# untitled.net
KiCad netlist of a schematic drawn in EAGLE
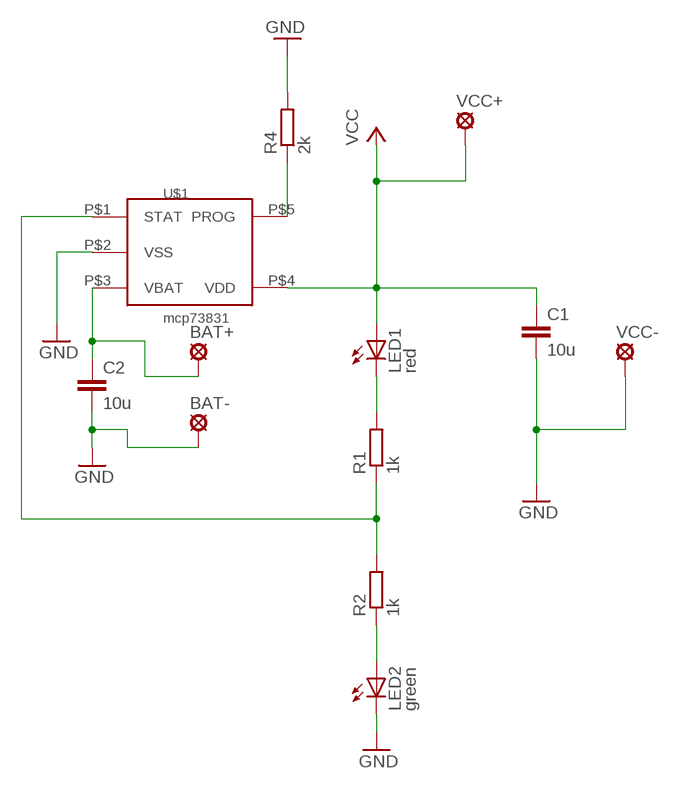
[diagram p0: schematic, sheet 1]

(export (version "E")
  (design (tool "Eeschema 10.0.6"))
  (components
    (comp (ref "BAT+")
      (value "LSP10")
      (footprint "eagle-import:LSP10")
      (libsource (lib "eagle-import") (part "LSP10"))
    )
    (comp (ref "BAT-")
      (value "LSP10")
      (footprint "eagle-import:LSP10")
      (libsource (lib "eagle-import") (part "LSP10"))
    )
    (comp (ref "C1")
      (value "10u")
      (footprint "eagle-import:C0805")
      (libsource (lib "eagle-import") (part "C-EUC0805"))
    )
    (comp (ref "C2")
      (value "10u")
      (footprint "eagle-import:C0805")
      (libsource (lib "eagle-import") (part "C-EUC0805"))
    )
    (comp (ref "LED1")
      (value "red")
      (footprint "eagle-import:CHIPLED_0805")
      (libsource (lib "eagle-import") (part "LEDCHIPLED_0805"))
    )
    (comp (ref "LED2")
      (value "green")
      (footprint "eagle-import:CHIPLED_0805")
      (libsource (lib "eagle-import") (part "LEDCHIPLED_0805"))
    )
    (comp (ref "R1")
      (value "1k")
      (footprint "eagle-import:M1206")
      (libsource (lib "eagle-import") (part "R-EU_M1206"))
    )
    (comp (ref "R2")
      (value "1k")
      (footprint "eagle-import:M1206")
      (libsource (lib "eagle-import") (part "R-EU_M1206"))
    )
    (comp (ref "R4")
      (value "2k")
      (footprint "eagle-import:M1206")
      (libsource (lib "eagle-import") (part "R-EU_M1206"))
    )
    (comp (ref "U$1")
      (value "mcp73831")
      (footprint "eagle-import:5PIN_SOT23")
      (libsource (lib "eagle-import") (part "MCP73831"))
    )
    (comp (ref "VCC+")
      (value "LSP10")
      (footprint "eagle-import:LSP10")
      (libsource (lib "eagle-import") (part "LSP10"))
    )
    (comp (ref "VCC-")
      (value "LSP10")
      (footprint "eagle-import:LSP10")
      (libsource (lib "eagle-import") (part "LSP10"))
    )
  )
  (nets
    (net (code "1") (name "GND") (class "Default")
      (node (ref "BAT-") (pin "MP") (pinfunction "MP_MP") (pintype "passive"))
      (node (ref "C1") (pin "2") (pinfunction "2_2") (pintype "passive"))
      (node (ref "C2") (pin "2") (pinfunction "2_2") (pintype "passive"))
      (node (ref "LED2") (pin "C") (pinfunction "C_C") (pintype "passive"))
      (node (ref "R4") (pin "2") (pinfunction "2_2") (pintype "passive"))
      (node (ref "U$1") (pin "P$2") (pinfunction "VSS_P$2") (pintype "bidirectional"))
      (node (ref "VCC-") (pin "MP") (pinfunction "MP_MP") (pintype "passive"))
    )
    (net (code "2") (name "Net-(LED1-PadC)") (class "Default")
      (node (ref "LED1") (pin "C") (pinfunction "C_C") (pintype "passive"))
      (node (ref "R1") (pin "2") (pinfunction "2_2") (pintype "passive"))
    )
    (net (code "3") (name "Net-(LED2-PadA)") (class "Default")
      (node (ref "LED2") (pin "A") (pinfunction "A_A") (pintype "passive"))
      (node (ref "R2") (pin "1") (pinfunction "1_1") (pintype "passive"))
    )
    (net (code "4") (name "Net-(U$1-PROG)") (class "Default")
      (node (ref "R4") (pin "1") (pinfunction "1_1") (pintype "passive"))
      (node (ref "U$1") (pin "P$5") (pinfunction "PROG_P$5") (pintype "bidirectional"))
    )
    (net (code "5") (name "Net-(U$1-STAT)") (class "Default")
      (node (ref "R1") (pin "1") (pinfunction "1_1") (pintype "passive"))
      (node (ref "R2") (pin "2") (pinfunction "2_2") (pintype "passive"))
      (node (ref "U$1") (pin "P$1") (pinfunction "STAT_P$1") (pintype "bidirectional"))
    )
    (net (code "6") (name "Net-(U$1-VBAT)") (class "Default")
      (node (ref "BAT+") (pin "MP") (pinfunction "MP_MP") (pintype "passive"))
      (node (ref "C2") (pin "1") (pinfunction "1_1") (pintype "passive"))
      (node (ref "U$1") (pin "P$3") (pinfunction "VBAT_P$3") (pintype "bidirectional"))
    )
    (net (code "7") (name "VCC") (class "Default")
      (node (ref "C1") (pin "1") (pinfunction "1_1") (pintype "passive"))
      (node (ref "LED1") (pin "A") (pinfunction "A_A") (pintype "passive"))
      (node (ref "U$1") (pin "P$4") (pinfunction "VDD_P$4") (pintype "bidirectional"))
      (node (ref "VCC+") (pin "MP") (pinfunction "MP_MP") (pintype "passive"))
    )
  )
)
